# power_mux-v10.net
KiCad netlist of a schematic drawn in EAGLE
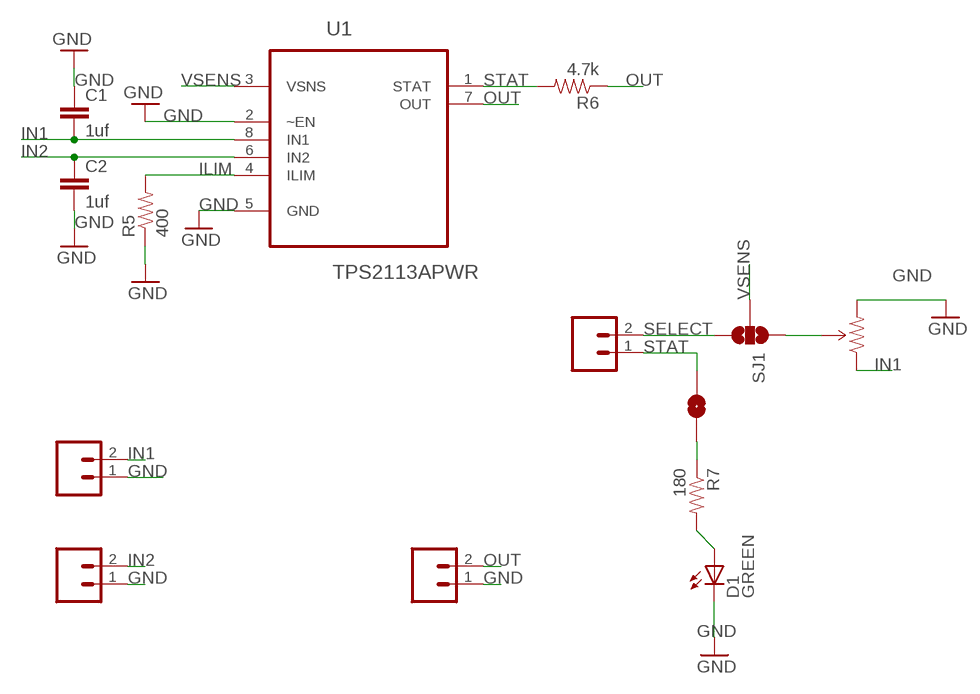
[diagram p0: schematic, sheet 1]

(export (version "E")
  (design (tool "Eeschema 10.0.6"))
  (components
    (comp (ref "C1")
      (value "1uf")
      (footprint "eagle-import:0603-CAP")
      (libsource (lib "eagle-import") (part "CAP0603-CAP"))
    )
    (comp (ref "C2")
      (value "1uf")
      (footprint "eagle-import:0603-CAP")
      (libsource (lib "eagle-import") (part "CAP0603-CAP"))
    )
    (comp (ref "D1")
      (value "GREEN")
      (footprint "eagle-import:LED-0603")
      (libsource (lib "eagle-import") (part "LED-GREEN0603"))
    )
    (comp (ref "JP3")
      (value "M021X02_NO_SILK")
      (footprint "eagle-import:1X02_NO_SILK")
      (libsource (lib "eagle-import") (part "M021X02_NO_SILK"))
    )
    (comp (ref "JP4")
      (value "M021X02_NO_SILK")
      (footprint "eagle-import:1X02_NO_SILK")
      (libsource (lib "eagle-import") (part "M021X02_NO_SILK"))
    )
    (comp (ref "JP5")
      (value "M021X02_NO_SILK")
      (footprint "eagle-import:1X02_NO_SILK")
      (libsource (lib "eagle-import") (part "M021X02_NO_SILK"))
    )
    (comp (ref "JP6")
      (value "M021X02_NO_SILK")
      (footprint "eagle-import:1X02_NO_SILK")
      (libsource (lib "eagle-import") (part "M021X02_NO_SILK"))
    )
    (comp (ref "R1")
      (value "TRIMPOT-PTH-KNOB")
      (footprint "eagle-import:3386U")
      (libsource (lib "eagle-import") (part "TRIMPOT-PTH-KNOB"))
    )
    (comp (ref "R5")
      (value "400")
      (footprint "eagle-import:0603-RES")
      (libsource (lib "eagle-import") (part "RESISTOR0603-RES"))
    )
    (comp (ref "R6")
      (value "4.7k")
      (footprint "eagle-import:0603-RES")
      (libsource (lib "eagle-import") (part "RESISTOR0603-RES"))
    )
    (comp (ref "R7")
      (value "180")
      (footprint "eagle-import:0603-RES")
      (libsource (lib "eagle-import") (part "RESISTOR0603-RES"))
    )
    (comp (ref "SJ1")
      (value "SOLDERJUMPER_2WAYPASTE1&2")
      (footprint "eagle-import:SJ_3_PASTE1&2")
      (libsource (lib "eagle-import") (part "SOLDERJUMPER_2WAYPASTE1&2"))
    )
    (comp (ref "SJ2")
      (value "SOLDERJUMPERNC2")
      (footprint "eagle-import:SJ_2S-NOTRACE")
      (libsource (lib "eagle-import") (part "SOLDERJUMPERNC2"))
    )
    (comp (ref "U1")
      (value "TPS2113APWR")
      (footprint "eagle-import:SOP65P640X120-8N")
      (libsource (lib "eagle-import") (part "TPS2113APWR"))
    )
  )
  (nets
    (net (code "1") (name "/ILIM") (class "Default")
      (node (ref "R5") (pin "2") (pinfunction "2_2") (pintype "passive"))
      (node (ref "U1") (pin "4") (pinfunction "ILIM_4") (pintype "input"))
    )
    (net (code "2") (name "/IN1") (class "Default")
      (node (ref "C1") (pin "2") (pinfunction "2_2") (pintype "passive"))
      (node (ref "JP3") (pin "2") (pinfunction "2_2") (pintype "passive"))
      (node (ref "R1") (pin "1") (pinfunction "CCW_1") (pintype "passive"))
      (node (ref "U1") (pin "8") (pinfunction "IN1_8") (pintype "input"))
    )
    (net (code "3") (name "/IN2") (class "Default")
      (node (ref "C2") (pin "1") (pinfunction "1_1") (pintype "passive"))
      (node (ref "JP4") (pin "2") (pinfunction "2_2") (pintype "passive"))
      (node (ref "U1") (pin "6") (pinfunction "IN2_6") (pintype "input"))
    )
    (net (code "4") (name "/OUT") (class "Default")
      (node (ref "JP6") (pin "2") (pinfunction "2_2") (pintype "passive"))
      (node (ref "R6") (pin "1") (pinfunction "1_1") (pintype "passive"))
      (node (ref "U1") (pin "7") (pinfunction "OUT_7") (pintype "output"))
    )
    (net (code "5") (name "/SELECT") (class "Default")
      (node (ref "JP5") (pin "2") (pinfunction "2_2") (pintype "passive"))
      (node (ref "SJ1") (pin "3") (pinfunction "3_3") (pintype "passive"))
    )
    (net (code "6") (name "/STAT") (class "Default")
      (node (ref "JP5") (pin "1") (pinfunction "1_1") (pintype "passive"))
      (node (ref "R6") (pin "2") (pinfunction "2_2") (pintype "passive"))
      (node (ref "SJ2") (pin "2") (pinfunction "2_2") (pintype "passive"))
      (node (ref "U1") (pin "1") (pinfunction "STAT_1") (pintype "output"))
    )
    (net (code "7") (name "/VSENS") (class "Default")
      (node (ref "SJ1") (pin "2") (pinfunction "2_2") (pintype "passive"))
      (node (ref "U1") (pin "3") (pinfunction "VSNS_3") (pintype "power_in"))
    )
    (net (code "8") (name "GND") (class "Default")
      (node (ref "C1") (pin "1") (pinfunction "1_1") (pintype "passive"))
      (node (ref "C2") (pin "2") (pinfunction "2_2") (pintype "passive"))
      (node (ref "D1") (pin "C") (pinfunction "C_C") (pintype "passive"))
      (node (ref "JP3") (pin "1") (pinfunction "1_1") (pintype "passive"))
      (node (ref "JP4") (pin "1") (pinfunction "1_1") (pintype "passive"))
      (node (ref "JP6") (pin "1") (pinfunction "1_1") (pintype "passive"))
      (node (ref "R1") (pin "3") (pinfunction "CW_3") (pintype "passive"))
      (node (ref "R5") (pin "1") (pinfunction "1_1") (pintype "passive"))
      (node (ref "U1") (pin "2") (pinfunction "~{EN}_2") (pintype "input"))
      (node (ref "U1") (pin "5") (pinfunction "GND_5") (pintype "passive"))
    )
    (net (code "9") (name "Net-(D1-PadA)") (class "Default")
      (node (ref "D1") (pin "A") (pinfunction "A_A") (pintype "passive"))
      (node (ref "R7") (pin "2") (pinfunction "2_2") (pintype "passive"))
    )
    (net (code "10") (name "Net-(R1-WIPER)") (class "Default")
      (node (ref "R1") (pin "2") (pinfunction "WIPER_2") (pintype "passive"))
      (node (ref "SJ1") (pin "1") (pinfunction "1_1") (pintype "passive"))
    )
    (net (code "11") (name "Net-(R7-Pad1)") (class "Default")
      (node (ref "R7") (pin "1") (pinfunction "1_1") (pintype "passive"))
      (node (ref "SJ2") (pin "1") (pinfunction "1_1") (pintype "passive"))
    )
  )
)
